# soil_res_scheme.net
KiCad netlist of a schematic drawn in EAGLE
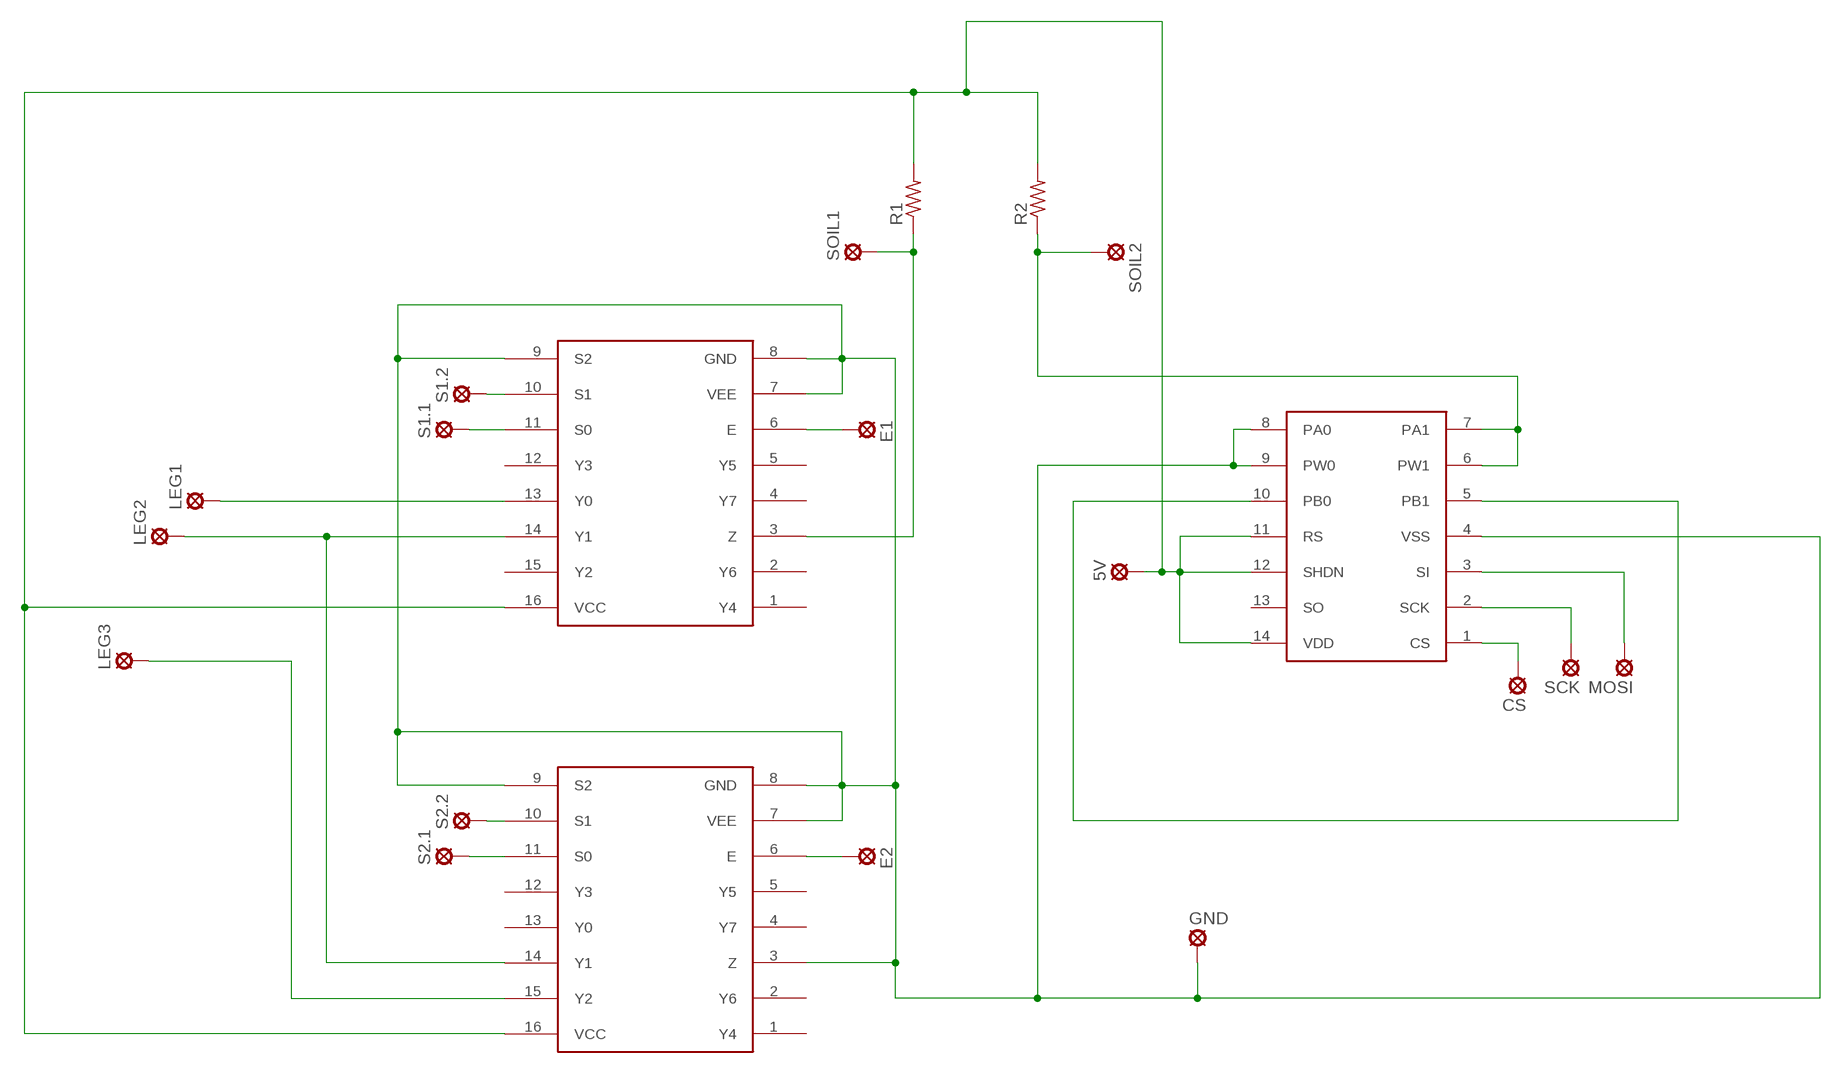
[diagram p0: schematic, sheet 1]

(export (version "E")
  (design (tool "Eeschema 10.0.6"))
  (components
    (comp (ref "5V")
      (value "LSP10")
      (footprint "eagle-import:LSP10")
      (libsource (lib "eagle-import") (part "LSP10"))
    )
    (comp (ref "CS")
      (value "LSP10")
      (footprint "eagle-import:LSP10")
      (libsource (lib "eagle-import") (part "LSP10"))
    )
    (comp (ref "E1")
      (value "LSP10")
      (footprint "eagle-import:LSP10")
      (libsource (lib "eagle-import") (part "LSP10"))
    )
    (comp (ref "E2")
      (value "LSP10")
      (footprint "eagle-import:LSP10")
      (libsource (lib "eagle-import") (part "LSP10"))
    )
    (comp (ref "GND")
      (value "LSP10")
      (footprint "eagle-import:LSP10")
      (libsource (lib "eagle-import") (part "LSP10"))
    )
    (comp (ref "LEG1")
      (value "LSP10")
      (footprint "eagle-import:LSP10")
      (libsource (lib "eagle-import") (part "LSP10"))
    )
    (comp (ref "LEG2")
      (value "LSP10")
      (footprint "eagle-import:LSP10")
      (libsource (lib "eagle-import") (part "LSP10"))
    )
    (comp (ref "LEG3")
      (value "LSP10")
      (footprint "eagle-import:LSP10")
      (libsource (lib "eagle-import") (part "LSP10"))
    )
    (comp (ref "MOSI")
      (value "LSP10")
      (footprint "eagle-import:LSP10")
      (libsource (lib "eagle-import") (part "LSP10"))
    )
    (comp (ref "R1")
      (value "R-US_0207/10")
      (footprint "eagle-import:0207_10")
      (libsource (lib "eagle-import") (part "R-US_0207/10"))
    )
    (comp (ref "R2")
      (value "R-US_0207/10")
      (footprint "eagle-import:0207_10")
      (libsource (lib "eagle-import") (part "R-US_0207/10"))
    )
    (comp (ref "S1.1")
      (value "LSP10")
      (footprint "eagle-import:LSP10")
      (libsource (lib "eagle-import") (part "LSP10"))
    )
    (comp (ref "S1.2")
      (value "LSP10")
      (footprint "eagle-import:LSP10")
      (libsource (lib "eagle-import") (part "LSP10"))
    )
    (comp (ref "S2.1")
      (value "LSP10")
      (footprint "eagle-import:LSP10")
      (libsource (lib "eagle-import") (part "LSP10"))
    )
    (comp (ref "S2.2")
      (value "LSP10")
      (footprint "eagle-import:LSP10")
      (libsource (lib "eagle-import") (part "LSP10"))
    )
    (comp (ref "SCK")
      (value "LSP10")
      (footprint "eagle-import:LSP10")
      (libsource (lib "eagle-import") (part "LSP10"))
    )
    (comp (ref "SOIL1")
      (value "LSP10")
      (footprint "eagle-import:LSP10")
      (libsource (lib "eagle-import") (part "LSP10"))
    )
    (comp (ref "SOIL2")
      (value "LSP10")
      (footprint "eagle-import:LSP10")
      (libsource (lib "eagle-import") (part "LSP10"))
    )
    (comp (ref "U$1")
      (value "MCP42100!")
      (footprint "eagle-import:DIL14")
      (libsource (lib "eagle-import") (part "MCP42100!"))
    )
    (comp (ref "U$2")
      (value "74HC4051!")
      (footprint "eagle-import:DIL16")
      (libsource (lib "eagle-import") (part "74HC4051!"))
    )
    (comp (ref "U$3")
      (value "74HC4051!")
      (footprint "eagle-import:DIL16")
      (libsource (lib "eagle-import") (part "74HC4051!"))
    )
  )
  (nets
    (net (code "1") (name "Net-(U$1-CS)") (class "Default")
      (node (ref "CS") (pin "MP") (pinfunction "MP_MP") (pintype "passive"))
      (node (ref "U$1") (pin "1") (pinfunction "CS_1") (pintype "bidirectional"))
    )
    (net (code "2") (name "Net-(U$1-PA0)") (class "Default")
      (node (ref "GND") (pin "MP") (pinfunction "MP_MP") (pintype "passive"))
      (node (ref "U$1") (pin "4") (pinfunction "VSS_4") (pintype "bidirectional"))
      (node (ref "U$1") (pin "8") (pinfunction "PA0_8") (pintype "bidirectional"))
      (node (ref "U$1") (pin "9") (pinfunction "PW0_9") (pintype "bidirectional"))
      (node (ref "U$2") (pin "7") (pinfunction "VEE_7") (pintype "bidirectional"))
      (node (ref "U$2") (pin "8") (pinfunction "GND_8") (pintype "bidirectional"))
      (node (ref "U$2") (pin "9") (pinfunction "S2_9") (pintype "bidirectional"))
      (node (ref "U$3") (pin "3") (pinfunction "Z_3") (pintype "bidirectional"))
      (node (ref "U$3") (pin "7") (pinfunction "VEE_7") (pintype "bidirectional"))
      (node (ref "U$3") (pin "8") (pinfunction "GND_8") (pintype "bidirectional"))
      (node (ref "U$3") (pin "9") (pinfunction "S2_9") (pintype "bidirectional"))
    )
    (net (code "3") (name "Net-(U$1-PA1)") (class "Default")
      (node (ref "R2") (pin "1") (pinfunction "1_1") (pintype "passive"))
      (node (ref "SOIL2") (pin "MP") (pinfunction "MP_MP") (pintype "passive"))
      (node (ref "U$1") (pin "6") (pinfunction "PW1_6") (pintype "bidirectional"))
      (node (ref "U$1") (pin "7") (pinfunction "PA1_7") (pintype "bidirectional"))
    )
    (net (code "4") (name "Net-(U$1-PB0)") (class "Default")
      (node (ref "U$1") (pin "10") (pinfunction "PB0_10") (pintype "bidirectional"))
      (node (ref "U$1") (pin "5") (pinfunction "PB1_5") (pintype "bidirectional"))
    )
    (net (code "5") (name "Net-(U$1-RS)") (class "Default")
      (node (ref "5V") (pin "MP") (pinfunction "MP_MP") (pintype "passive"))
      (node (ref "R1") (pin "2") (pinfunction "2_2") (pintype "passive"))
      (node (ref "R2") (pin "2") (pinfunction "2_2") (pintype "passive"))
      (node (ref "U$1") (pin "11") (pinfunction "RS_11") (pintype "bidirectional"))
      (node (ref "U$1") (pin "12") (pinfunction "SHDN_12") (pintype "bidirectional"))
      (node (ref "U$1") (pin "14") (pinfunction "VDD_14") (pintype "bidirectional"))
      (node (ref "U$2") (pin "16") (pinfunction "VCC_16") (pintype "bidirectional"))
      (node (ref "U$3") (pin "16") (pinfunction "VCC_16") (pintype "bidirectional"))
    )
    (net (code "6") (name "Net-(U$1-SCK)") (class "Default")
      (node (ref "SCK") (pin "MP") (pinfunction "MP_MP") (pintype "passive"))
      (node (ref "U$1") (pin "2") (pinfunction "SCK_2") (pintype "bidirectional"))
    )
    (net (code "7") (name "Net-(U$1-SI)") (class "Default")
      (node (ref "MOSI") (pin "MP") (pinfunction "MP_MP") (pintype "passive"))
      (node (ref "U$1") (pin "3") (pinfunction "SI_3") (pintype "bidirectional"))
    )
    (net (code "8") (name "Net-(U$2-E)") (class "Default")
      (node (ref "E1") (pin "MP") (pinfunction "MP_MP") (pintype "passive"))
      (node (ref "U$2") (pin "6") (pinfunction "E_6") (pintype "bidirectional"))
    )
    (net (code "9") (name "Net-(U$2-S0)") (class "Default")
      (node (ref "S1.1") (pin "MP") (pinfunction "MP_MP") (pintype "passive"))
      (node (ref "U$2") (pin "11") (pinfunction "S0_11") (pintype "bidirectional"))
    )
    (net (code "10") (name "Net-(U$2-S1)") (class "Default")
      (node (ref "S1.2") (pin "MP") (pinfunction "MP_MP") (pintype "passive"))
      (node (ref "U$2") (pin "10") (pinfunction "S1_10") (pintype "bidirectional"))
    )
    (net (code "11") (name "Net-(U$2-Y0)") (class "Default")
      (node (ref "LEG1") (pin "MP") (pinfunction "MP_MP") (pintype "passive"))
      (node (ref "U$2") (pin "13") (pinfunction "Y0_13") (pintype "bidirectional"))
    )
    (net (code "12") (name "Net-(U$2-Y1)") (class "Default")
      (node (ref "LEG2") (pin "MP") (pinfunction "MP_MP") (pintype "passive"))
      (node (ref "U$2") (pin "14") (pinfunction "Y1_14") (pintype "bidirectional"))
      (node (ref "U$3") (pin "14") (pinfunction "Y1_14") (pintype "bidirectional"))
    )
    (net (code "13") (name "Net-(U$2-Z)") (class "Default")
      (node (ref "R1") (pin "1") (pinfunction "1_1") (pintype "passive"))
      (node (ref "SOIL1") (pin "MP") (pinfunction "MP_MP") (pintype "passive"))
      (node (ref "U$2") (pin "3") (pinfunction "Z_3") (pintype "bidirectional"))
    )
    (net (code "14") (name "Net-(U$3-E)") (class "Default")
      (node (ref "E2") (pin "MP") (pinfunction "MP_MP") (pintype "passive"))
      (node (ref "U$3") (pin "6") (pinfunction "E_6") (pintype "bidirectional"))
    )
    (net (code "15") (name "Net-(U$3-S0)") (class "Default")
      (node (ref "S2.1") (pin "MP") (pinfunction "MP_MP") (pintype "passive"))
      (node (ref "U$3") (pin "11") (pinfunction "S0_11") (pintype "bidirectional"))
    )
    (net (code "16") (name "Net-(U$3-S1)") (class "Default")
      (node (ref "S2.2") (pin "MP") (pinfunction "MP_MP") (pintype "passive"))
      (node (ref "U$3") (pin "10") (pinfunction "S1_10") (pintype "bidirectional"))
    )
    (net (code "17") (name "Net-(U$3-Y2)") (class "Default")
      (node (ref "LEG3") (pin "MP") (pinfunction "MP_MP") (pintype "passive"))
      (node (ref "U$3") (pin "15") (pinfunction "Y2_15") (pintype "bidirectional"))
    )
    (net (code "18") (name "unconnected-(U$1-SO-Pad13)") (class "Default")
      (node (ref "U$1") (pin "13") (pinfunction "SO_13") (pintype "bidirectional"))
    )
    (net (code "19") (name "unconnected-(U$2-Y2-Pad15)") (class "Default")
      (node (ref "U$2") (pin "15") (pinfunction "Y2_15") (pintype "bidirectional"))
    )
    (net (code "20") (name "unconnected-(U$2-Y3-Pad12)") (class "Default")
      (node (ref "U$2") (pin "12") (pinfunction "Y3_12") (pintype "bidirectional"))
    )
    (net (code "21") (name "unconnected-(U$2-Y4-Pad1)") (class "Default")
      (node (ref "U$2") (pin "1") (pinfunction "Y4_1") (pintype "bidirectional"))
    )
    (net (code "22") (name "unconnected-(U$2-Y5-Pad5)") (class "Default")
      (node (ref "U$2") (pin "5") (pinfunction "Y5_5") (pintype "bidirectional"))
    )
    (net (code "23") (name "unconnected-(U$2-Y6-Pad2)") (class "Default")
      (node (ref "U$2") (pin "2") (pinfunction "Y6_2") (pintype "bidirectional"))
    )
    (net (code "24") (name "unconnected-(U$2-Y7-Pad4)") (class "Default")
      (node (ref "U$2") (pin "4") (pinfunction "Y7_4") (pintype "bidirectional"))
    )
    (net (code "25") (name "unconnected-(U$3-Y0-Pad13)") (class "Default")
      (node (ref "U$3") (pin "13") (pinfunction "Y0_13") (pintype "bidirectional"))
    )
    (net (code "26") (name "unconnected-(U$3-Y3-Pad12)") (class "Default")
      (node (ref "U$3") (pin "12") (pinfunction "Y3_12") (pintype "bidirectional"))
    )
    (net (code "27") (name "unconnected-(U$3-Y4-Pad1)") (class "Default")
      (node (ref "U$3") (pin "1") (pinfunction "Y4_1") (pintype "bidirectional"))
    )
    (net (code "28") (name "unconnected-(U$3-Y5-Pad5)") (class "Default")
      (node (ref "U$3") (pin "5") (pinfunction "Y5_5") (pintype "bidirectional"))
    )
    (net (code "29") (name "unconnected-(U$3-Y6-Pad2)") (class "Default")
      (node (ref "U$3") (pin "2") (pinfunction "Y6_2") (pintype "bidirectional"))
    )
    (net (code "30") (name "unconnected-(U$3-Y7-Pad4)") (class "Default")
      (node (ref "U$3") (pin "4") (pinfunction "Y7_4") (pintype "bidirectional"))
    )
  )
)
